# RELAY.net
KiCad netlist of a schematic drawn in Altium Designer
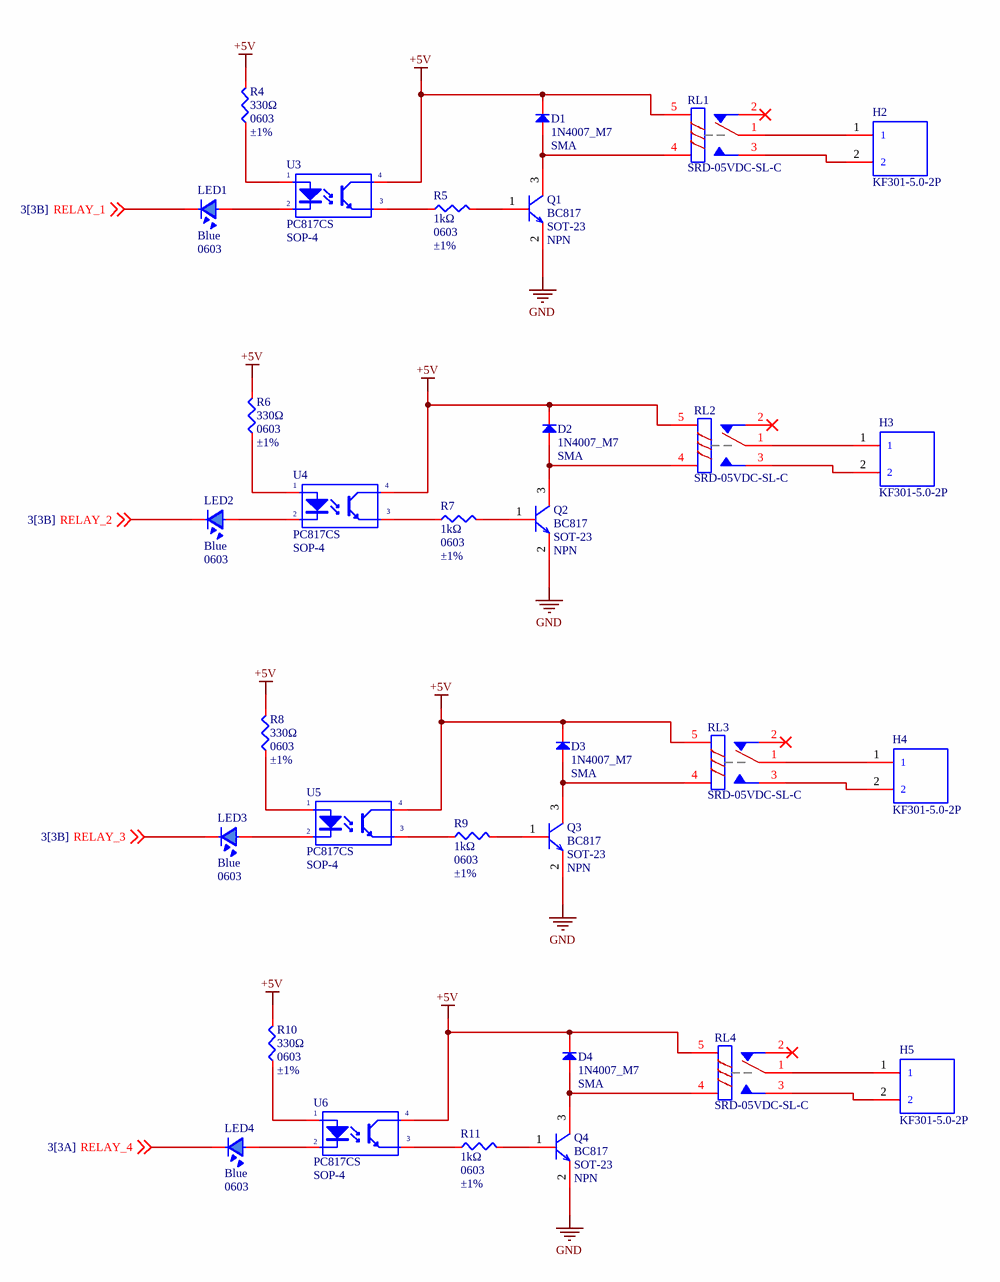
[diagram p0: RELAY.SchDoc]

(export (version "E")
  (design (tool "Eeschema 10.0.6"))
  (components
    (comp (ref "D1")
      (value "1N4007_M7")
      (footprint "SMA(DO-214AC)")
      (description "1A 1V@1A 1kV SMA Diodes - General Purpose ROHS")
      (fields
        (field (name "MANUFACTURER") "JSMSEMI")
        (field (name "MFR. PART") "1N4007 M7")
        (field (name "PACKAGE") "SMA")
      )
      (libsource (lib "DIODE") (part "1N4007_M7"))
    )
    (comp (ref "D2")
      (value "1N4007_M7")
      (footprint "SMA(DO-214AC)")
      (description "1A 1V@1A 1kV SMA Diodes - General Purpose ROHS")
      (fields
        (field (name "MANUFACTURER") "JSMSEMI")
        (field (name "MFR. PART") "1N4007 M7")
        (field (name "PACKAGE") "SMA")
      )
      (libsource (lib "DIODE") (part "1N4007_M7"))
    )
    (comp (ref "D3")
      (value "1N4007_M7")
      (footprint "SMA(DO-214AC)")
      (description "1A 1V@1A 1kV SMA Diodes - General Purpose ROHS")
      (fields
        (field (name "MANUFACTURER") "JSMSEMI")
        (field (name "MFR. PART") "1N4007 M7")
        (field (name "PACKAGE") "SMA")
      )
      (libsource (lib "DIODE") (part "1N4007_M7"))
    )
    (comp (ref "D4")
      (value "1N4007_M7")
      (footprint "SMA(DO-214AC)")
      (description "1A 1V@1A 1kV SMA Diodes - General Purpose ROHS")
      (fields
        (field (name "MANUFACTURER") "JSMSEMI")
        (field (name "MFR. PART") "1N4007 M7")
        (field (name "PACKAGE") "SMA")
      )
      (libsource (lib "DIODE") (part "1N4007_M7"))
    )
    (comp (ref "H2")
      (value "KF301-5.0-2P")
      (footprint "CONN-TH_P5.00_KF301-5.0-2P")
      (fields (field (name "MANUFACTURER") "Cixi Kefa Elec") (field (name "LCSC PART") "C474881"))
      (libsource (lib "CONNECTER") (part "KF301-5.0-2P"))
    )
    (comp (ref "H3")
      (value "KF301-5.0-2P")
      (footprint "CONN-TH_P5.00_KF301-5.0-2P")
      (fields (field (name "MANUFACTURER") "Cixi Kefa Elec") (field (name "LCSC PART") "C474881"))
      (libsource (lib "CONNECTER") (part "KF301-5.0-2P"))
    )
    (comp (ref "H4")
      (value "KF301-5.0-2P")
      (footprint "CONN-TH_P5.00_KF301-5.0-2P")
      (fields (field (name "MANUFACTURER") "Cixi Kefa Elec") (field (name "LCSC PART") "C474881"))
      (libsource (lib "CONNECTER") (part "KF301-5.0-2P"))
    )
    (comp (ref "H5")
      (value "KF301-5.0-2P")
      (footprint "CONN-TH_P5.00_KF301-5.0-2P")
      (fields (field (name "MANUFACTURER") "Cixi Kefa Elec") (field (name "LCSC PART") "C474881"))
      (libsource (lib "CONNECTER") (part "KF301-5.0-2P"))
    )
    (comp (ref "LED1")
      (value "Blue")
      (footprint "LED0603_BLUE")
      (description "2mA 24mcd Water Clear -40℃~+85℃ 470nm Blue 130° 120mW 2.65V 0603 LED Indication - Discrete ROHS")
      (fields
        (field (name "MANUFACTURER") "Kingbright")
        (field (name "MFR. PART") "APT1608LVBC/D")
        (field (name "PACKAGE") "0603")
      )
      (libsource (lib "LED") (part "LED0603_Blue"))
    )
    (comp (ref "LED2")
      (value "Blue")
      (footprint "LED0603_BLUE")
      (description "2mA 24mcd Water Clear -40℃~+85℃ 470nm Blue 130° 120mW 2.65V 0603 LED Indication - Discrete ROHS")
      (fields
        (field (name "MANUFACTURER") "Kingbright")
        (field (name "MFR. PART") "APT1608LVBC/D")
        (field (name "PACKAGE") "0603")
      )
      (libsource (lib "LED") (part "LED0603_Blue"))
    )
    (comp (ref "LED3")
      (value "Blue")
      (footprint "LED0603_BLUE")
      (description "2mA 24mcd Water Clear -40℃~+85℃ 470nm Blue 130° 120mW 2.65V 0603 LED Indication - Discrete ROHS")
      (fields
        (field (name "MANUFACTURER") "Kingbright")
        (field (name "MFR. PART") "APT1608LVBC/D")
        (field (name "PACKAGE") "0603")
      )
      (libsource (lib "LED") (part "LED0603_Blue"))
    )
    (comp (ref "LED4")
      (value "Blue")
      (footprint "LED0603_BLUE")
      (description "2mA 24mcd Water Clear -40℃~+85℃ 470nm Blue 130° 120mW 2.65V 0603 LED Indication - Discrete ROHS")
      (fields
        (field (name "MANUFACTURER") "Kingbright")
        (field (name "MFR. PART") "APT1608LVBC/D")
        (field (name "PACKAGE") "0603")
      )
      (libsource (lib "LED") (part "LED0603_Blue"))
    )
    (comp (ref "Q1")
      (value "BC817")
      (footprint "SOT-23")
      (description "345mW 45V 250@100mA,1V 500mA NPN SOT-23 Single Bipolar Transistors ROHS")
      (fields
        (field (name "MANUFACTURER") "Nexperia")
        (field (name "MFR. PART") "BC817-40,215")
        (field (name "PACKAGE") "SOT-23")
        (field (name "TYPE") "NPN")
      )
      (libsource (lib "BJT and FET") (part "BC817"))
    )
    (comp (ref "Q2")
      (value "BC817")
      (footprint "SOT-23")
      (description "345mW 45V 250@100mA,1V 500mA NPN SOT-23 Single Bipolar Transistors ROHS")
      (fields
        (field (name "MANUFACTURER") "Nexperia")
        (field (name "MFR. PART") "BC817-40,215")
        (field (name "PACKAGE") "SOT-23")
        (field (name "TYPE") "NPN")
      )
      (libsource (lib "BJT and FET") (part "BC817"))
    )
    (comp (ref "Q3")
      (value "BC817")
      (footprint "SOT-23")
      (description "345mW 45V 250@100mA,1V 500mA NPN SOT-23 Single Bipolar Transistors ROHS")
      (fields
        (field (name "MANUFACTURER") "Nexperia")
        (field (name "MFR. PART") "BC817-40,215")
        (field (name "PACKAGE") "SOT-23")
        (field (name "TYPE") "NPN")
      )
      (libsource (lib "BJT and FET") (part "BC817"))
    )
    (comp (ref "Q4")
      (value "BC817")
      (footprint "SOT-23")
      (description "345mW 45V 250@100mA,1V 500mA NPN SOT-23 Single Bipolar Transistors ROHS")
      (fields
        (field (name "MANUFACTURER") "Nexperia")
        (field (name "MFR. PART") "BC817-40,215")
        (field (name "PACKAGE") "SOT-23")
        (field (name "TYPE") "NPN")
      )
      (libsource (lib "BJT and FET") (part "BC817"))
    )
    (comp (ref "R4")
      (value "330Ω")
      (footprint "R0603")
      (description "100mW Thick Film Resistor 75V ±100ppm/℃ ±1% 330Ω 0603 Chip Resistor - Surface Mount ROHS")
      (fields
        (field (name "MANUFACTURER") "YAGEO")
        (field (name "MFR. PART") "RC0603FR-07330RL")
        (field (name "PACKAGE") "0603")
        (field (name "TOLERANCE") "±1%")
      )
      (libsource (lib "Resistor") (part "R0603_330Ω_±1%"))
    )
    (comp (ref "R5")
      (value "1kΩ")
      (footprint "R0603")
      (description "100mW Thick Film Resistor 75V ±100ppm/℃ ±1% 1kΩ 0603 Chip Resistor - Surface Mount ROHS")
      (fields
        (field (name "MANUFACTURER") "YAGEO")
        (field (name "MFR. PART") "RC0603FR-071KL")
        (field (name "PACKAGE") "0603")
        (field (name "TOLERANCE") "±1%")
      )
      (libsource (lib "Resistor") (part "R0603_1kΩ_±1%"))
    )
    (comp (ref "R6")
      (value "330Ω")
      (footprint "R0603")
      (description "100mW Thick Film Resistor 75V ±100ppm/℃ ±1% 330Ω 0603 Chip Resistor - Surface Mount ROHS")
      (fields
        (field (name "MANUFACTURER") "YAGEO")
        (field (name "MFR. PART") "RC0603FR-07330RL")
        (field (name "PACKAGE") "0603")
        (field (name "TOLERANCE") "±1%")
      )
      (libsource (lib "Resistor") (part "R0603_330Ω_±1%"))
    )
    (comp (ref "R7")
      (value "1kΩ")
      (footprint "R0603")
      (description "100mW Thick Film Resistor 75V ±100ppm/℃ ±1% 1kΩ 0603 Chip Resistor - Surface Mount ROHS")
      (fields
        (field (name "MANUFACTURER") "YAGEO")
        (field (name "MFR. PART") "RC0603FR-071KL")
        (field (name "PACKAGE") "0603")
        (field (name "TOLERANCE") "±1%")
      )
      (libsource (lib "Resistor") (part "R0603_1kΩ_±1%"))
    )
    (comp (ref "R8")
      (value "330Ω")
      (footprint "R0603")
      (description "100mW Thick Film Resistor 75V ±100ppm/℃ ±1% 330Ω 0603 Chip Resistor - Surface Mount ROHS")
      (fields
        (field (name "MANUFACTURER") "YAGEO")
        (field (name "MFR. PART") "RC0603FR-07330RL")
        (field (name "PACKAGE") "0603")
        (field (name "TOLERANCE") "±1%")
      )
      (libsource (lib "Resistor") (part "R0603_330Ω_±1%"))
    )
    (comp (ref "R9")
      (value "1kΩ")
      (footprint "R0603")
      (description "100mW Thick Film Resistor 75V ±100ppm/℃ ±1% 1kΩ 0603 Chip Resistor - Surface Mount ROHS")
      (fields
        (field (name "MANUFACTURER") "YAGEO")
        (field (name "MFR. PART") "RC0603FR-071KL")
        (field (name "PACKAGE") "0603")
        (field (name "TOLERANCE") "±1%")
      )
      (libsource (lib "Resistor") (part "R0603_1kΩ_±1%"))
    )
    (comp (ref "R10")
      (value "330Ω")
      (footprint "R0603")
      (description "100mW Thick Film Resistor 75V ±100ppm/℃ ±1% 330Ω 0603 Chip Resistor - Surface Mount ROHS")
      (fields
        (field (name "MANUFACTURER") "YAGEO")
        (field (name "MFR. PART") "RC0603FR-07330RL")
        (field (name "PACKAGE") "0603")
        (field (name "TOLERANCE") "±1%")
      )
      (libsource (lib "Resistor") (part "R0603_330Ω_±1%"))
    )
    (comp (ref "R11")
      (value "1kΩ")
      (footprint "R0603")
      (description "100mW Thick Film Resistor 75V ±100ppm/℃ ±1% 1kΩ 0603 Chip Resistor - Surface Mount ROHS")
      (fields
        (field (name "MANUFACTURER") "YAGEO")
        (field (name "MFR. PART") "RC0603FR-071KL")
        (field (name "PACKAGE") "0603")
        (field (name "TOLERANCE") "±1%")
      )
      (libsource (lib "Resistor") (part "R0603_1kΩ_±1%"))
    )
    (comp (ref "RL1")
      (value "SRD-05VDC-SL-C")
      (footprint "Through Hole,15.6x19.2mm")
      (description "250V@AC 5V 15A 1 Form C: 1C (SPDT-CO) Through Hole,15.6x19.2mm Power Relays ROHS")
      (fields (field (name "MANUFACTURER") "Songle Relay") (field (name "LCSC PART") "C35449"))
      (libsource (lib "RELAY") (part "SRD-05VDC-SL-C"))
    )
    (comp (ref "RL2")
      (value "SRD-05VDC-SL-C")
      (footprint "Through Hole,15.6x19.2mm")
      (description "250V@AC 5V 15A 1 Form C: 1C (SPDT-CO) Through Hole,15.6x19.2mm Power Relays ROHS")
      (fields (field (name "MANUFACTURER") "Songle Relay") (field (name "LCSC PART") "C35449"))
      (libsource (lib "RELAY") (part "SRD-05VDC-SL-C"))
    )
    (comp (ref "RL3")
      (value "SRD-05VDC-SL-C")
      (footprint "Through Hole,15.6x19.2mm")
      (description "250V@AC 5V 15A 1 Form C: 1C (SPDT-CO) Through Hole,15.6x19.2mm Power Relays ROHS")
      (fields (field (name "MANUFACTURER") "Songle Relay") (field (name "LCSC PART") "C35449"))
      (libsource (lib "RELAY") (part "SRD-05VDC-SL-C"))
    )
    (comp (ref "RL4")
      (value "SRD-05VDC-SL-C")
      (footprint "Through Hole,15.6x19.2mm")
      (description "250V@AC 5V 15A 1 Form C: 1C (SPDT-CO) Through Hole,15.6x19.2mm Power Relays ROHS")
      (fields (field (name "MANUFACTURER") "Songle Relay") (field (name "LCSC PART") "C35449"))
      (libsource (lib "RELAY") (part "SRD-05VDC-SL-C"))
    )
    (comp (ref "U3")
      (value "PC817CS")
      (footprint "SOP-4")
      (description "50mA 200mV@1mA,20mA 80V 6V 1.2V DC SOP-4 Transistor, Photovoltaic Output Optoisolators ROHS")
      (fields
        (field (name "MANUFACTURER") "AOTE")
        (field (name "LCSC PART") "C20612591")
        (field (name "PACKAGE") "SOP-4")
      )
      (libsource (lib "OPTO") (part "PC817CS"))
    )
    (comp (ref "U4")
      (value "PC817CS")
      (footprint "SOP-4")
      (description "50mA 200mV@1mA,20mA 80V 6V 1.2V DC SOP-4 Transistor, Photovoltaic Output Optoisolators ROHS")
      (fields
        (field (name "MANUFACTURER") "AOTE")
        (field (name "LCSC PART") "C20612591")
        (field (name "PACKAGE") "SOP-4")
      )
      (libsource (lib "OPTO") (part "PC817CS"))
    )
    (comp (ref "U5")
      (value "PC817CS")
      (footprint "SOP-4")
      (description "50mA 200mV@1mA,20mA 80V 6V 1.2V DC SOP-4 Transistor, Photovoltaic Output Optoisolators ROHS")
      (fields
        (field (name "MANUFACTURER") "AOTE")
        (field (name "LCSC PART") "C20612591")
        (field (name "PACKAGE") "SOP-4")
      )
      (libsource (lib "OPTO") (part "PC817CS"))
    )
    (comp (ref "U6")
      (value "PC817CS")
      (footprint "SOP-4")
      (description "50mA 200mV@1mA,20mA 80V 6V 1.2V DC SOP-4 Transistor, Photovoltaic Output Optoisolators ROHS")
      (fields
        (field (name "MANUFACTURER") "AOTE")
        (field (name "LCSC PART") "C20612591")
        (field (name "PACKAGE") "SOP-4")
      )
      (libsource (lib "OPTO") (part "PC817CS"))
    )
  )
  (nets
    (net (code "1") (name "+5V") (class "Default")
      (node (ref "D1") (pin "1") (pinfunction "1_1") (pintype "passive"))
      (node (ref "D2") (pin "1") (pinfunction "1_1") (pintype "passive"))
      (node (ref "D3") (pin "1") (pinfunction "1_1") (pintype "passive"))
      (node (ref "D4") (pin "1") (pinfunction "1_1") (pintype "passive"))
      (node (ref "R10") (pin "2") (pinfunction "2_2") (pintype "passive"))
      (node (ref "R4") (pin "2") (pinfunction "2_2") (pintype "passive"))
      (node (ref "R6") (pin "2") (pinfunction "2_2") (pintype "passive"))
      (node (ref "R8") (pin "2") (pinfunction "2_2") (pintype "passive"))
      (node (ref "RL1") (pin "5") (pinfunction "5_5") (pintype "passive"))
      (node (ref "RL2") (pin "5") (pinfunction "5_5") (pintype "passive"))
      (node (ref "RL3") (pin "5") (pinfunction "5_5") (pintype "passive"))
      (node (ref "RL4") (pin "5") (pinfunction "5_5") (pintype "passive"))
      (node (ref "U3") (pin "4") (pinfunction "C_4") (pintype "passive"))
      (node (ref "U4") (pin "4") (pinfunction "C_4") (pintype "passive"))
      (node (ref "U5") (pin "4") (pinfunction "C_4") (pintype "passive"))
      (node (ref "U6") (pin "4") (pinfunction "C_4") (pintype "passive"))
    )
    (net (code "2") (name "GND") (class "Default")
      (node (ref "Q1") (pin "2") (pinfunction "E_2") (pintype "passive"))
      (node (ref "Q2") (pin "2") (pinfunction "E_2") (pintype "passive"))
      (node (ref "Q3") (pin "2") (pinfunction "E_2") (pintype "passive"))
      (node (ref "Q4") (pin "2") (pinfunction "E_2") (pintype "passive"))
    )
    (net (code "3") (name "Net-(H2-Pad1)") (class "Default")
      (node (ref "H2") (pin "1") (pinfunction "1_1") (pintype "passive"))
      (node (ref "RL1") (pin "1") (pinfunction "1_1") (pintype "passive"))
    )
    (net (code "4") (name "Net-(H2-Pad2)") (class "Default")
      (node (ref "H2") (pin "2") (pinfunction "2_2") (pintype "passive"))
      (node (ref "RL1") (pin "3") (pinfunction "3_3") (pintype "passive"))
    )
    (net (code "5") (name "Net-(H3-Pad1)") (class "Default")
      (node (ref "H3") (pin "1") (pinfunction "1_1") (pintype "passive"))
      (node (ref "RL2") (pin "1") (pinfunction "1_1") (pintype "passive"))
    )
    (net (code "6") (name "Net-(H3-Pad2)") (class "Default")
      (node (ref "H3") (pin "2") (pinfunction "2_2") (pintype "passive"))
      (node (ref "RL2") (pin "3") (pinfunction "3_3") (pintype "passive"))
    )
    (net (code "7") (name "Net-(H4-Pad1)") (class "Default")
      (node (ref "H4") (pin "1") (pinfunction "1_1") (pintype "passive"))
      (node (ref "RL3") (pin "1") (pinfunction "1_1") (pintype "passive"))
    )
    (net (code "8") (name "Net-(H4-Pad2)") (class "Default")
      (node (ref "H4") (pin "2") (pinfunction "2_2") (pintype "passive"))
      (node (ref "RL3") (pin "3") (pinfunction "3_3") (pintype "passive"))
    )
    (net (code "9") (name "Net-(H5-Pad1)") (class "Default")
      (node (ref "H5") (pin "1") (pinfunction "1_1") (pintype "passive"))
      (node (ref "RL4") (pin "1") (pinfunction "1_1") (pintype "passive"))
    )
    (net (code "10") (name "Net-(H5-Pad2)") (class "Default")
      (node (ref "H5") (pin "2") (pinfunction "2_2") (pintype "passive"))
      (node (ref "RL4") (pin "3") (pinfunction "3_3") (pintype "passive"))
    )
    (net (code "11") (name "Net-(Q1-B)") (class "Default")
      (node (ref "Q1") (pin "1") (pinfunction "B_1") (pintype "passive"))
      (node (ref "R5") (pin "2") (pinfunction "2_2") (pintype "passive"))
    )
    (net (code "12") (name "Net-(Q1-C)") (class "Default")
      (node (ref "D1") (pin "2") (pinfunction "2_2") (pintype "passive"))
      (node (ref "Q1") (pin "3") (pinfunction "C_3") (pintype "passive"))
      (node (ref "RL1") (pin "4") (pinfunction "4_4") (pintype "passive"))
    )
    (net (code "13") (name "Net-(Q2-B)") (class "Default")
      (node (ref "Q2") (pin "1") (pinfunction "B_1") (pintype "passive"))
      (node (ref "R7") (pin "2") (pinfunction "2_2") (pintype "passive"))
    )
    (net (code "14") (name "Net-(Q2-C)") (class "Default")
      (node (ref "D2") (pin "2") (pinfunction "2_2") (pintype "passive"))
      (node (ref "Q2") (pin "3") (pinfunction "C_3") (pintype "passive"))
      (node (ref "RL2") (pin "4") (pinfunction "4_4") (pintype "passive"))
    )
    (net (code "15") (name "Net-(Q3-B)") (class "Default")
      (node (ref "Q3") (pin "1") (pinfunction "B_1") (pintype "passive"))
      (node (ref "R9") (pin "2") (pinfunction "2_2") (pintype "passive"))
    )
    (net (code "16") (name "Net-(Q3-C)") (class "Default")
      (node (ref "D3") (pin "2") (pinfunction "2_2") (pintype "passive"))
      (node (ref "Q3") (pin "3") (pinfunction "C_3") (pintype "passive"))
      (node (ref "RL3") (pin "4") (pinfunction "4_4") (pintype "passive"))
    )
    (net (code "17") (name "Net-(Q4-B)") (class "Default")
      (node (ref "Q4") (pin "1") (pinfunction "B_1") (pintype "passive"))
      (node (ref "R11") (pin "2") (pinfunction "2_2") (pintype "passive"))
    )
    (net (code "18") (name "Net-(Q4-C)") (class "Default")
      (node (ref "D4") (pin "2") (pinfunction "2_2") (pintype "passive"))
      (node (ref "Q4") (pin "3") (pinfunction "C_3") (pintype "passive"))
      (node (ref "RL4") (pin "4") (pinfunction "4_4") (pintype "passive"))
    )
    (net (code "19") (name "Net-(U3-A)") (class "Default")
      (node (ref "R4") (pin "1") (pinfunction "1_1") (pintype "passive"))
      (node (ref "U3") (pin "1") (pinfunction "A_1") (pintype "passive"))
    )
    (net (code "20") (name "Net-(U3-E)") (class "Default")
      (node (ref "R5") (pin "1") (pinfunction "1_1") (pintype "passive"))
      (node (ref "U3") (pin "3") (pinfunction "E_3") (pintype "passive"))
    )
    (net (code "21") (name "Net-(U3-K)") (class "Default")
      (node (ref "LED1") (pin "1") (pinfunction "1_1") (pintype "passive"))
      (node (ref "U3") (pin "2") (pinfunction "K_2") (pintype "passive"))
    )
    (net (code "22") (name "Net-(U4-A)") (class "Default")
      (node (ref "R6") (pin "1") (pinfunction "1_1") (pintype "passive"))
      (node (ref "U4") (pin "1") (pinfunction "A_1") (pintype "passive"))
    )
    (net (code "23") (name "Net-(U4-E)") (class "Default")
      (node (ref "R7") (pin "1") (pinfunction "1_1") (pintype "passive"))
      (node (ref "U4") (pin "3") (pinfunction "E_3") (pintype "passive"))
    )
    (net (code "24") (name "Net-(U4-K)") (class "Default")
      (node (ref "LED2") (pin "1") (pinfunction "1_1") (pintype "passive"))
      (node (ref "U4") (pin "2") (pinfunction "K_2") (pintype "passive"))
    )
    (net (code "25") (name "Net-(U5-A)") (class "Default")
      (node (ref "R8") (pin "1") (pinfunction "1_1") (pintype "passive"))
      (node (ref "U5") (pin "1") (pinfunction "A_1") (pintype "passive"))
    )
    (net (code "26") (name "Net-(U5-E)") (class "Default")
      (node (ref "R9") (pin "1") (pinfunction "1_1") (pintype "passive"))
      (node (ref "U5") (pin "3") (pinfunction "E_3") (pintype "passive"))
    )
    (net (code "27") (name "Net-(U5-K)") (class "Default")
      (node (ref "LED3") (pin "1") (pinfunction "1_1") (pintype "passive"))
      (node (ref "U5") (pin "2") (pinfunction "K_2") (pintype "passive"))
    )
    (net (code "28") (name "Net-(U6-A)") (class "Default")
      (node (ref "R10") (pin "1") (pinfunction "1_1") (pintype "passive"))
      (node (ref "U6") (pin "1") (pinfunction "A_1") (pintype "passive"))
    )
    (net (code "29") (name "Net-(U6-E)") (class "Default")
      (node (ref "R11") (pin "1") (pinfunction "1_1") (pintype "passive"))
      (node (ref "U6") (pin "3") (pinfunction "E_3") (pintype "passive"))
    )
    (net (code "30") (name "Net-(U6-K)") (class "Default")
      (node (ref "LED4") (pin "1") (pinfunction "1_1") (pintype "passive"))
      (node (ref "U6") (pin "2") (pinfunction "K_2") (pintype "passive"))
    )
    (net (code "31") (name "RELAY_1") (class "Default")
      (node (ref "LED1") (pin "2") (pinfunction "2_2") (pintype "passive"))
    )
    (net (code "32") (name "RELAY_2") (class "Default")
      (node (ref "LED2") (pin "2") (pinfunction "2_2") (pintype "passive"))
    )
    (net (code "33") (name "RELAY_3") (class "Default")
      (node (ref "LED3") (pin "2") (pinfunction "2_2") (pintype "passive"))
    )
    (net (code "34") (name "RELAY_4") (class "Default")
      (node (ref "LED4") (pin "2") (pinfunction "2_2") (pintype "passive"))
    )
    (net (code "35") (name "unconnected-(RL1-Pad2)") (class "Default")
      (node (ref "RL1") (pin "2") (pinfunction "2_2") (pintype "passive+no_connect"))
    )
    (net (code "36") (name "unconnected-(RL2-Pad2)") (class "Default")
      (node (ref "RL2") (pin "2") (pinfunction "2_2") (pintype "passive+no_connect"))
    )
    (net (code "37") (name "unconnected-(RL3-Pad2)") (class "Default")
      (node (ref "RL3") (pin "2") (pinfunction "2_2") (pintype "passive+no_connect"))
    )
    (net (code "38") (name "unconnected-(RL4-Pad2)") (class "Default")
      (node (ref "RL4") (pin "2") (pinfunction "2_2") (pintype "passive+no_connect"))
    )
  )
)
